# F1E_Rev_0_9.net
KiCad netlist of a schematic drawn in EAGLE
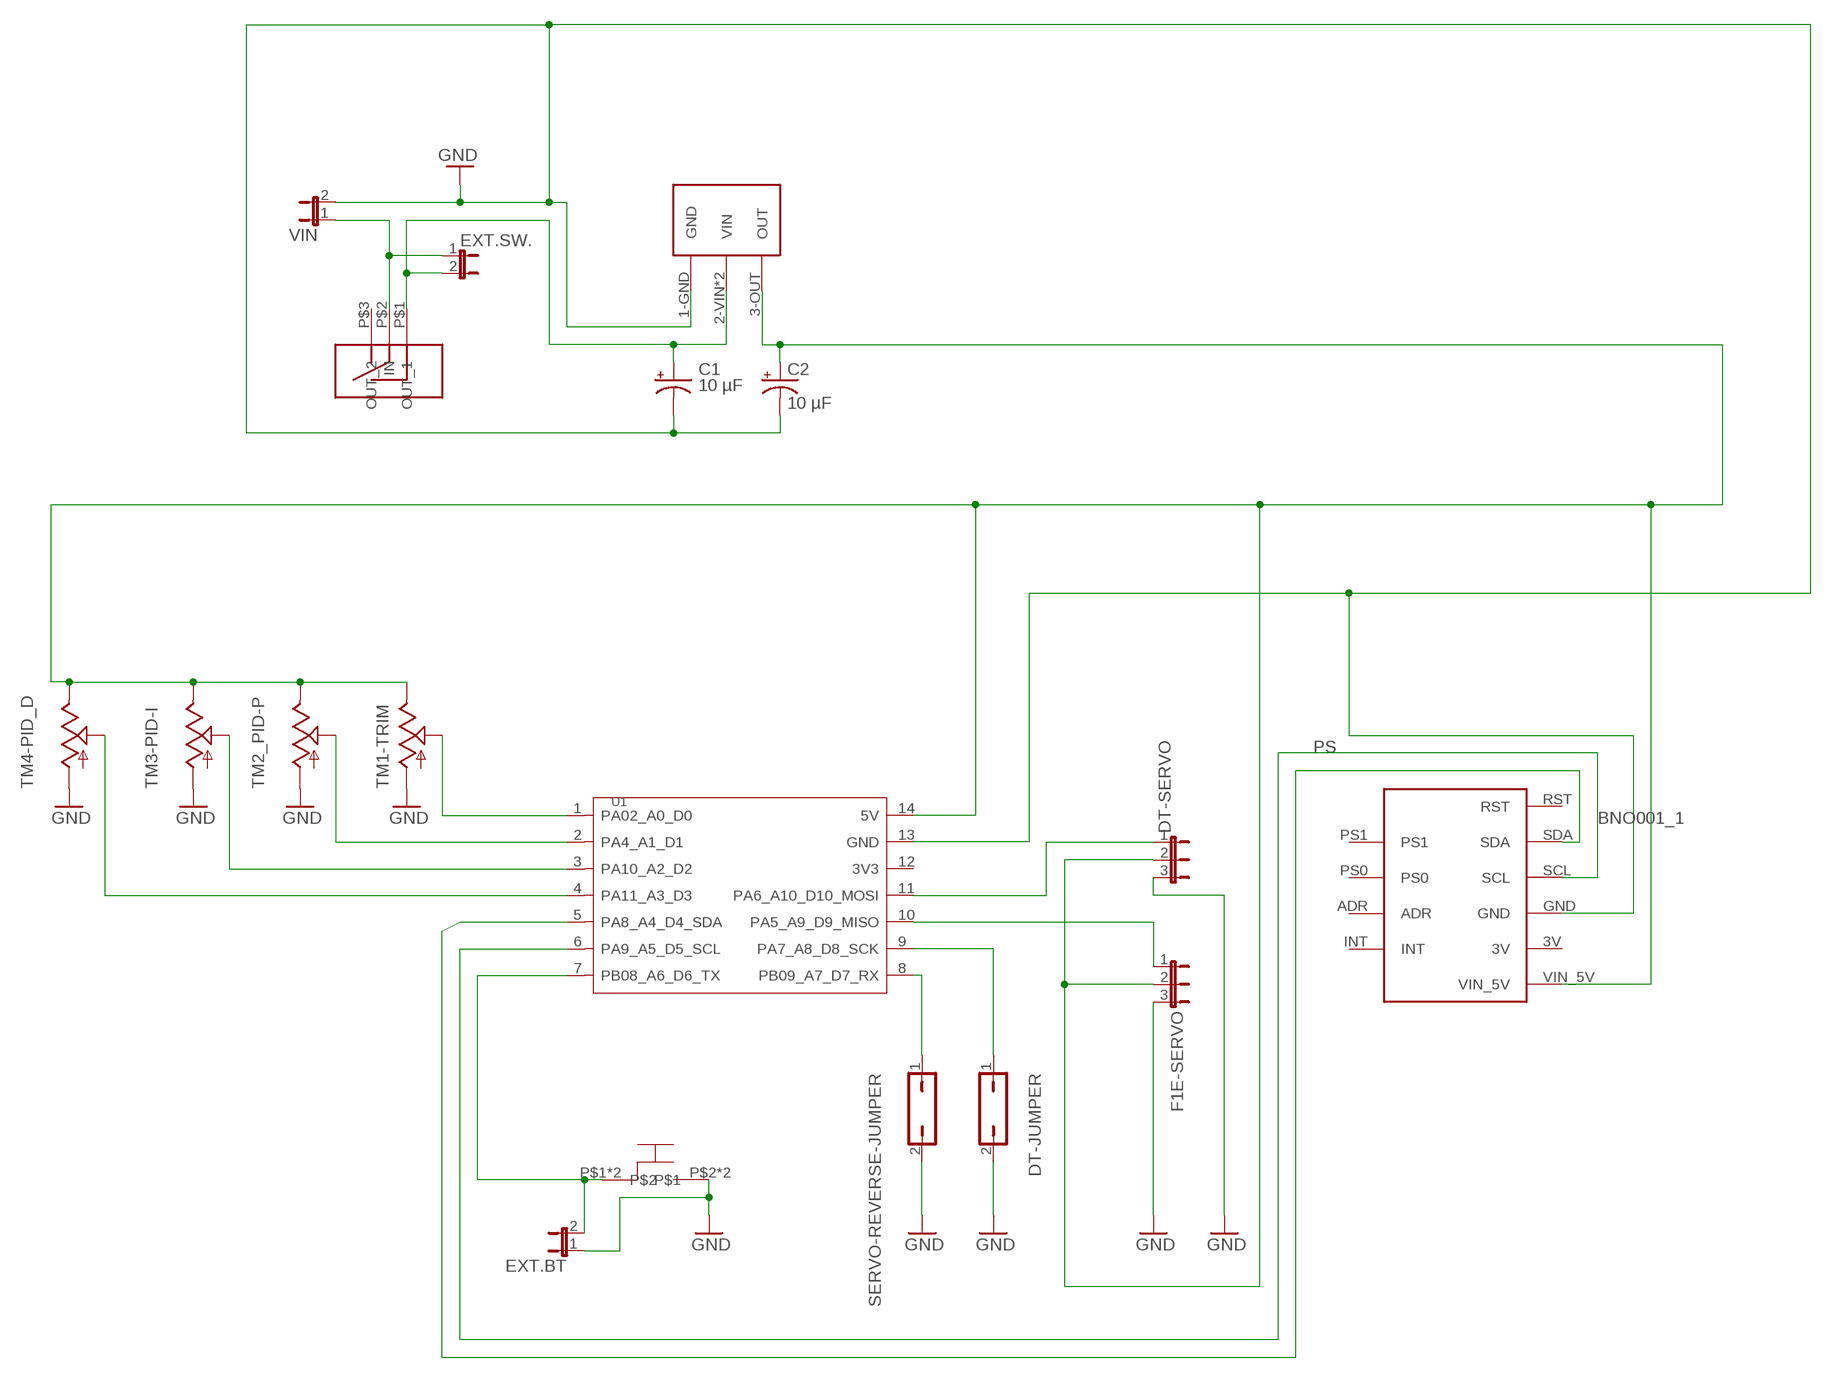
[diagram p0: schematic, sheet 1]

(export (version "E")
  (design (tool "Eeschema 10.0.6"))
  (components
    (comp (ref "BNO001_1")
      (value "PS")
      (footprint "eagle-import:PS")
      (libsource (lib "eagle-import") (part "PS"))
    )
    (comp (ref "C1")
      (value "10 µF")
      (footprint "eagle-import:153CLV-0405")
      (libsource (lib "eagle-import") (part "CPOL-US153CLV-0405"))
    )
    (comp (ref "C2")
      (value "10 µF")
      (footprint "eagle-import:153CLV-0405")
      (libsource (lib "eagle-import") (part "CPOL-US153CLV-0405"))
    )
    (comp (ref "DT-JUMPER")
      (value "JP1Q")
      (footprint "eagle-import:JP1")
      (libsource (lib "eagle-import") (part "JP1Q"))
    )
    (comp (ref "DT-SERVO")
      (value "JP2E")
      (footprint "eagle-import:JP2")
      (libsource (lib "eagle-import") (part "JP2E"))
    )
    (comp (ref "EXT.BT")
      (value "JP1E")
      (footprint "eagle-import:JP1")
      (libsource (lib "eagle-import") (part "JP1E"))
    )
    (comp (ref "EXT.SW.")
      (value "JP1E")
      (footprint "eagle-import:JP1")
      (libsource (lib "eagle-import") (part "JP1E"))
    )
    (comp (ref "F1E-SERVO")
      (value "JP2W")
      (footprint "eagle-import:JP2W")
      (libsource (lib "eagle-import") (part "JP2W"))
    )
    (comp (ref "SERVO-REVERSE-JUMPER")
      (value "JP1Q")
      (footprint "eagle-import:JP1")
      (libsource (lib "eagle-import") (part "JP1Q"))
    )
    (comp (ref "TM1-TRIM")
      (value "TRIM")
      (footprint "eagle-import:6MM")
      (libsource (lib "eagle-import") (part "TRIM"))
    )
    (comp (ref "TM2_PID-P")
      (value "TRIM")
      (footprint "eagle-import:6MM")
      (libsource (lib "eagle-import") (part "TRIM"))
    )
    (comp (ref "TM3-PID-I")
      (value "TRIM")
      (footprint "eagle-import:6MM")
      (libsource (lib "eagle-import") (part "TRIM"))
    )
    (comp (ref "TM4-PID_D")
      (value "TRIM")
      (footprint "eagle-import:6MM")
      (libsource (lib "eagle-import") (part "TRIM"))
    )
    (comp (ref "U$1")
      (value "PS_HT7350_SOT89")
      (footprint "eagle-import:PS_HT7350_SOT89")
      (libsource (lib "eagle-import") (part "PS_HT7350_SOT89"))
    )
    (comp (ref "U$2")
      (value "PA_BUTTON")
      (footprint "eagle-import:PS_BUTTON")
      (libsource (lib "eagle-import") (part "PA_BUTTON"))
    )
    (comp (ref "U$3")
      (value "PS_PWR")
      (footprint "eagle-import:PS_PW")
      (libsource (lib "eagle-import") (part "PS_PWR"))
    )
    (comp (ref "U1")
      (value "MOUDLE-SEEEDUINO-XIAO")
      (footprint "eagle-import:MOUDLE14P-2.54-21X17.8MM")
      (libsource (lib "eagle-import") (part "MOUDLE-SEEEDUINO-XIAO"))
    )
    (comp (ref "VIN")
      (value "JP1E")
      (footprint "eagle-import:JP1")
      (libsource (lib "eagle-import") (part "JP1E"))
    )
  )
  (nets
    (net (code "1") (name "/3V") (class "Default")
      (node (ref "BNO001_1") (pin "3V") (pinfunction "3V_3V") (pintype "power_in"))
    )
    (net (code "2") (name "GND") (class "Default")
      (node (ref "BNO001_1") (pin "GND") (pinfunction "GND_GND") (pintype "input"))
      (node (ref "C1") (pin "-") (pinfunction "-_-") (pintype "passive"))
      (node (ref "C2") (pin "-") (pinfunction "-_-") (pintype "passive"))
      (node (ref "DT-JUMPER") (pin "2") (pinfunction "2_2") (pintype "passive"))
      (node (ref "DT-SERVO") (pin "3") (pinfunction "3_3") (pintype "passive"))
      (node (ref "EXT.BT") (pin "1") (pinfunction "1_1") (pintype "passive"))
      (node (ref "F1E-SERVO") (pin "3") (pinfunction "3_3") (pintype "passive"))
      (node (ref "SERVO-REVERSE-JUMPER") (pin "2") (pinfunction "2_2") (pintype "passive"))
      (node (ref "TM1-TRIM") (pin "A") (pinfunction "A_A") (pintype "passive"))
      (node (ref "TM2_PID-P") (pin "A") (pinfunction "A_A") (pintype "passive"))
      (node (ref "TM3-PID-I") (pin "A") (pinfunction "A_A") (pintype "passive"))
      (node (ref "TM4-PID_D") (pin "A") (pinfunction "A_A") (pintype "passive"))
      (node (ref "U$1") (pin "1-GND") (pinfunction "GND_1-GND") (pintype "input"))
      (node (ref "U$2") (pin "P$2") (pinfunction "P$2_P$2") (pintype "bidirectional"))
      (node (ref "U$2") (pin "P$3") (pinfunction "P$2_P$3") (pintype "bidirectional"))
      (node (ref "U1") (pin "13") (pinfunction "GND_13") (pintype "bidirectional"))
      (node (ref "VIN") (pin "2") (pinfunction "2_2") (pintype "passive"))
    )
    (net (code "3") (name "Net-(U$1-OUT)") (class "Default")
      (node (ref "BNO001_1") (pin "VIN_5V") (pinfunction "VIN_5V_VIN_5V") (pintype "power_in"))
      (node (ref "C2") (pin "+") (pinfunction "+_+") (pintype "passive"))
      (node (ref "DT-SERVO") (pin "2") (pinfunction "2_2") (pintype "passive"))
      (node (ref "F1E-SERVO") (pin "2") (pinfunction "2_2") (pintype "passive"))
      (node (ref "TM1-TRIM") (pin "E") (pinfunction "E_E") (pintype "passive"))
      (node (ref "TM2_PID-P") (pin "E") (pinfunction "E_E") (pintype "passive"))
      (node (ref "TM3-PID-I") (pin "E") (pinfunction "E_E") (pintype "passive"))
      (node (ref "TM4-PID_D") (pin "E") (pinfunction "E_E") (pintype "passive"))
      (node (ref "U$1") (pin "3-OUT") (pinfunction "OUT_3-OUT") (pintype "output"))
      (node (ref "U1") (pin "14") (pinfunction "5V_14") (pintype "bidirectional"))
    )
    (net (code "4") (name "Net-(U$3-IN)") (class "Default")
      (node (ref "EXT.SW.") (pin "1") (pinfunction "1_1") (pintype "passive"))
      (node (ref "U$3") (pin "P$2") (pinfunction "IN_P$2") (pintype "input"))
      (node (ref "VIN") (pin "1") (pinfunction "1_1") (pintype "passive"))
    )
    (net (code "5") (name "Net-(U$3-OUT_1)") (class "Default")
      (node (ref "C1") (pin "+") (pinfunction "+_+") (pintype "passive"))
      (node (ref "EXT.SW.") (pin "2") (pinfunction "2_2") (pintype "passive"))
      (node (ref "U$1") (pin "2-VIN") (pinfunction "VIN_2-VIN") (pintype "power_in"))
      (node (ref "U$1") (pin "VIN") (pinfunction "VIN_VIN") (pintype "power_in"))
      (node (ref "U$3") (pin "P$1") (pinfunction "OUT_1_P$1") (pintype "output"))
    )
    (net (code "6") (name "Net-(U1-PA02_A0_D0)") (class "Default")
      (node (ref "TM1-TRIM") (pin "S") (pinfunction "S_S") (pintype "passive"))
      (node (ref "U1") (pin "1") (pinfunction "PA02_A0_D0_1") (pintype "bidirectional"))
    )
    (net (code "7") (name "Net-(U1-PA4_A1_D1)") (class "Default")
      (node (ref "TM2_PID-P") (pin "S") (pinfunction "S_S") (pintype "passive"))
      (node (ref "U1") (pin "2") (pinfunction "PA4_A1_D1_2") (pintype "bidirectional"))
    )
    (net (code "8") (name "Net-(U1-PA5_A9_D9_MISO)") (class "Default")
      (node (ref "F1E-SERVO") (pin "1") (pinfunction "1_1") (pintype "passive"))
      (node (ref "U1") (pin "10") (pinfunction "PA5_A9_D9_MISO_10") (pintype "bidirectional"))
    )
    (net (code "9") (name "Net-(U1-PA6_A10_D10_MOSI)") (class "Default")
      (node (ref "DT-SERVO") (pin "1") (pinfunction "1_1") (pintype "passive"))
      (node (ref "U1") (pin "11") (pinfunction "PA6_A10_D10_MOSI_11") (pintype "bidirectional"))
    )
    (net (code "10") (name "Net-(U1-PA7_A8_D8_SCK)") (class "Default")
      (node (ref "DT-JUMPER") (pin "1") (pinfunction "1_1") (pintype "passive"))
      (node (ref "U1") (pin "9") (pinfunction "PA7_A8_D8_SCK_9") (pintype "bidirectional"))
    )
    (net (code "11") (name "Net-(U1-PA8_A4_D4_SDA)") (class "Default")
      (node (ref "BNO001_1") (pin "SDA") (pinfunction "SDA_SDA") (pintype "bidirectional"))
      (node (ref "U1") (pin "5") (pinfunction "PA8_A4_D4_SDA_5") (pintype "bidirectional"))
    )
    (net (code "12") (name "Net-(U1-PA9_A5_D5_SCL)") (class "Default")
      (node (ref "BNO001_1") (pin "SCL") (pinfunction "SCL_SCL") (pintype "bidirectional"))
      (node (ref "U1") (pin "6") (pinfunction "PA9_A5_D5_SCL_6") (pintype "bidirectional"))
    )
    (net (code "13") (name "Net-(U1-PA10_A2_D2)") (class "Default")
      (node (ref "TM3-PID-I") (pin "S") (pinfunction "S_S") (pintype "passive"))
      (node (ref "U1") (pin "3") (pinfunction "PA10_A2_D2_3") (pintype "bidirectional"))
    )
    (net (code "14") (name "Net-(U1-PA11_A3_D3)") (class "Default")
      (node (ref "TM4-PID_D") (pin "S") (pinfunction "S_S") (pintype "passive"))
      (node (ref "U1") (pin "4") (pinfunction "PA11_A3_D3_4") (pintype "bidirectional"))
    )
    (net (code "15") (name "Net-(U1-PB08_A6_D6_TX)") (class "Default")
      (node (ref "EXT.BT") (pin "2") (pinfunction "2_2") (pintype "passive"))
      (node (ref "U$2") (pin "P$1") (pinfunction "P$1_P$1") (pintype "bidirectional"))
      (node (ref "U$2") (pin "P$4") (pinfunction "P$1_P$4") (pintype "bidirectional"))
      (node (ref "U1") (pin "7") (pinfunction "PB08_A6_D6_TX_7") (pintype "bidirectional"))
    )
    (net (code "16") (name "Net-(U1-PB09_A7_D7_RX)") (class "Default")
      (node (ref "SERVO-REVERSE-JUMPER") (pin "1") (pinfunction "1_1") (pintype "passive"))
      (node (ref "U1") (pin "8") (pinfunction "PB09_A7_D7_RX_8") (pintype "bidirectional"))
    )
    (net (code "17") (name "unconnected-(BNO001_1-PadADR)") (class "Default")
      (node (ref "BNO001_1") (pin "ADR") (pinfunction "ADR_ADR") (pintype "bidirectional"))
    )
    (net (code "18") (name "unconnected-(BNO001_1-PadINT)") (class "Default")
      (node (ref "BNO001_1") (pin "INT") (pinfunction "INT_INT") (pintype "bidirectional"))
    )
    (net (code "19") (name "unconnected-(BNO001_1-PadPS0)") (class "Default")
      (node (ref "BNO001_1") (pin "PS0") (pinfunction "PS0_PS0") (pintype "bidirectional"))
    )
    (net (code "20") (name "unconnected-(BNO001_1-PadPS1)") (class "Default")
      (node (ref "BNO001_1") (pin "PS1") (pinfunction "PS1_PS1") (pintype "bidirectional"))
    )
    (net (code "21") (name "unconnected-(BNO001_1-PadRST)") (class "Default")
      (node (ref "BNO001_1") (pin "RST") (pinfunction "RST_RST") (pintype "bidirectional"))
    )
    (net (code "22") (name "unconnected-(U$3-OUT_2-PadP$3)") (class "Default")
      (node (ref "U$3") (pin "P$3") (pinfunction "OUT_2_P$3") (pintype "output"))
    )
    (net (code "23") (name "unconnected-(U1-3V3-Pad12)") (class "Default")
      (node (ref "U1") (pin "12") (pinfunction "3V3_12") (pintype "bidirectional"))
    )
  )
)
